# sound.net
KiCad netlist of a schematic drawn in EAGLE
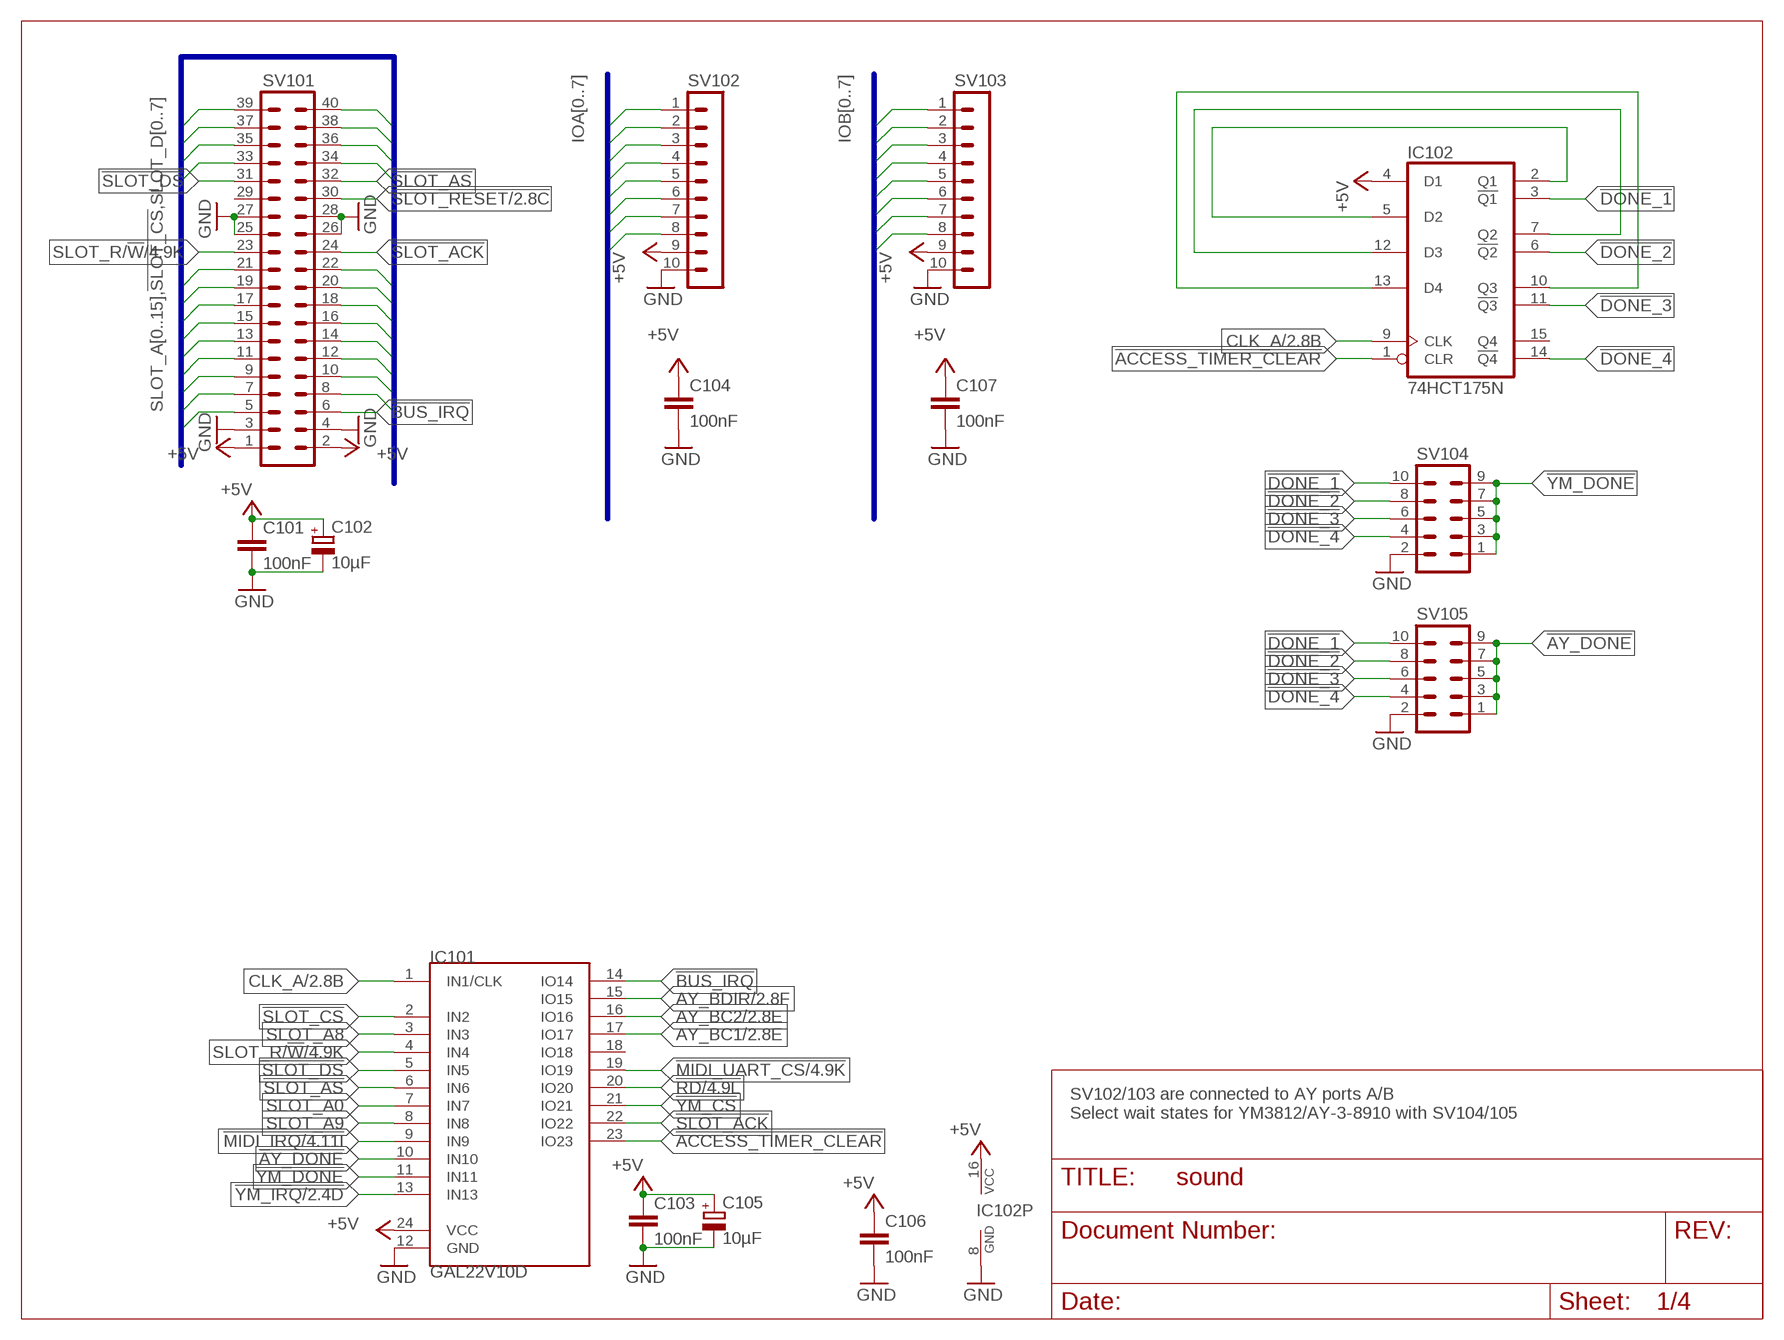
[diagram p0: schematic, sheet 1]
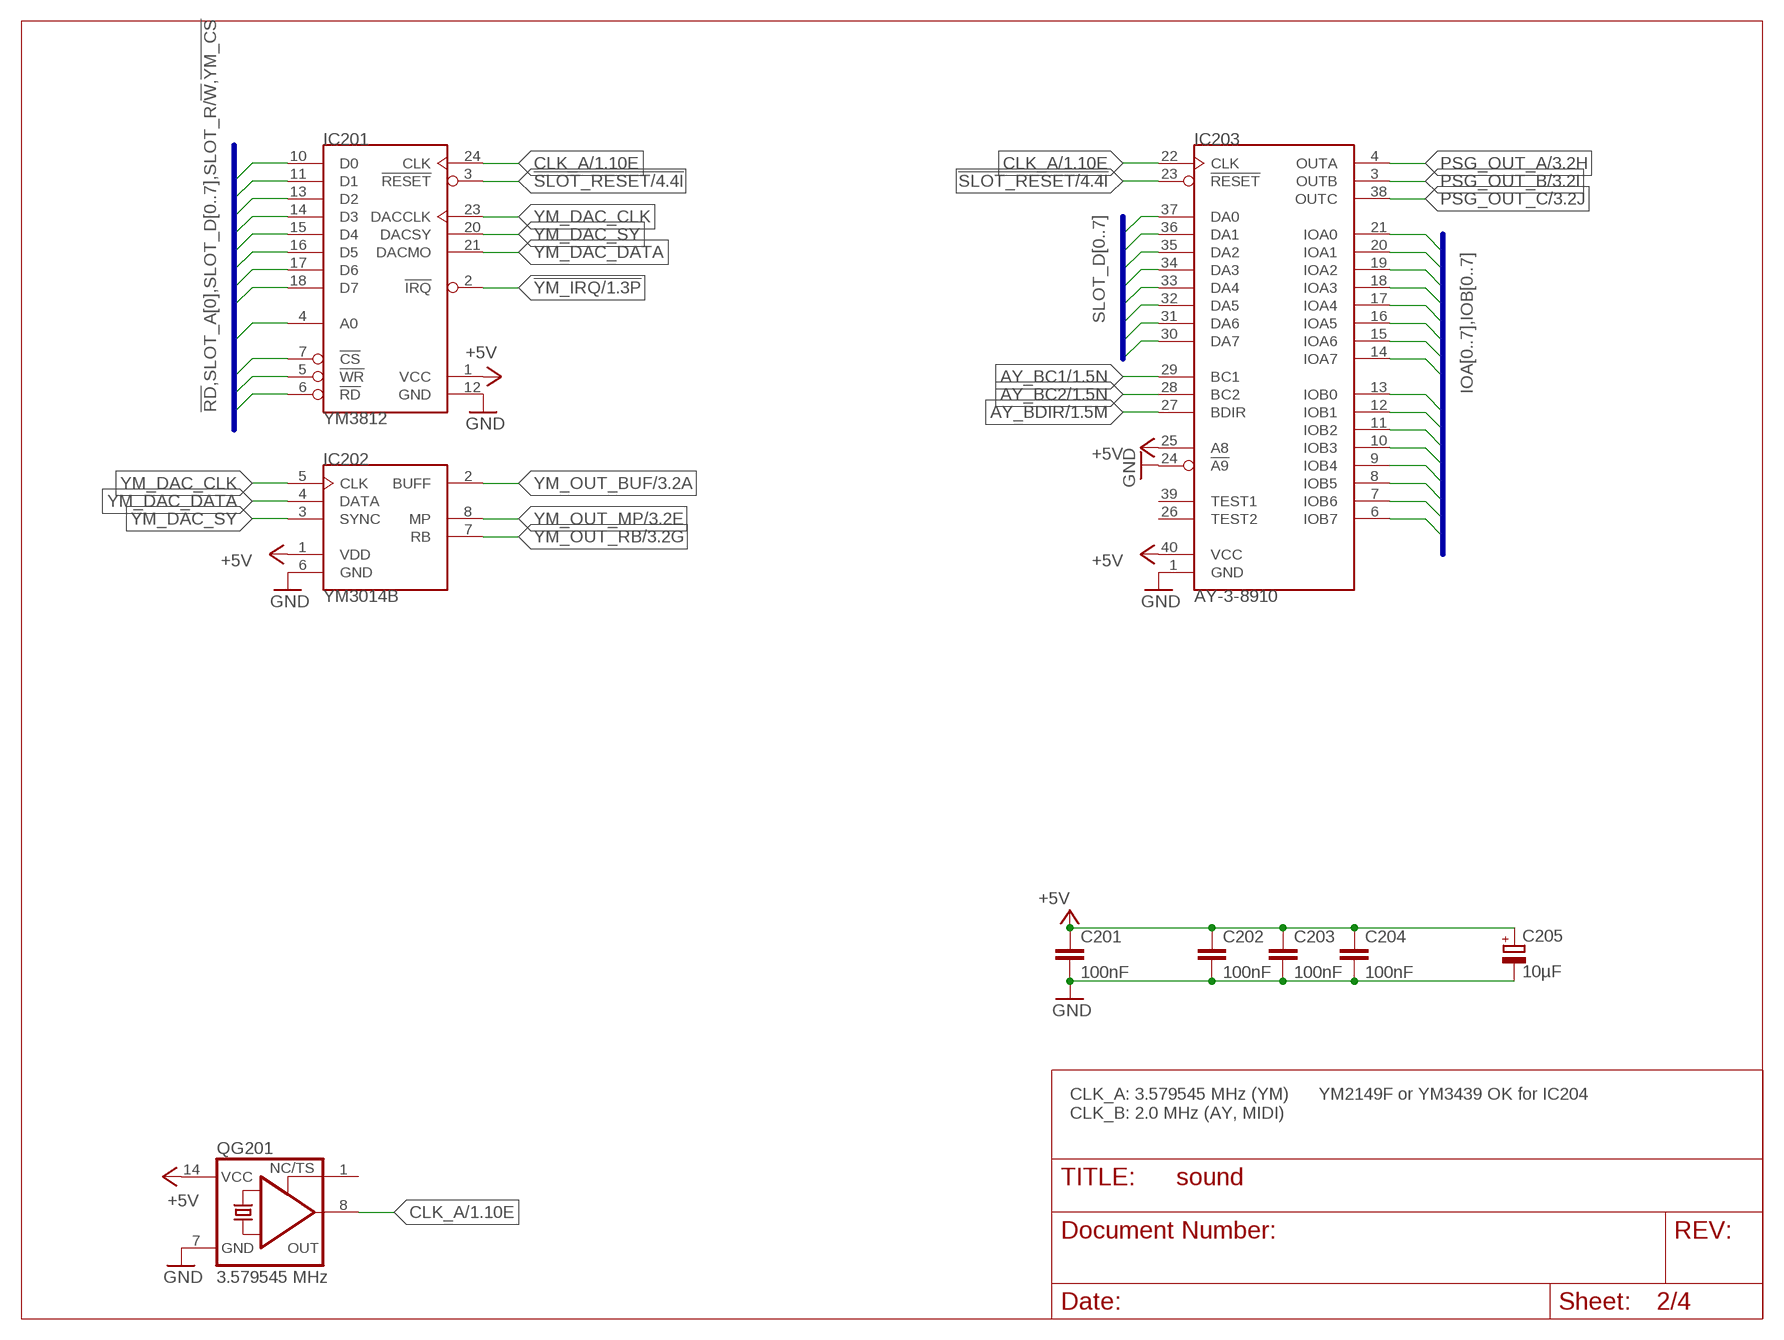
[diagram p1: schematic, sheet 2]
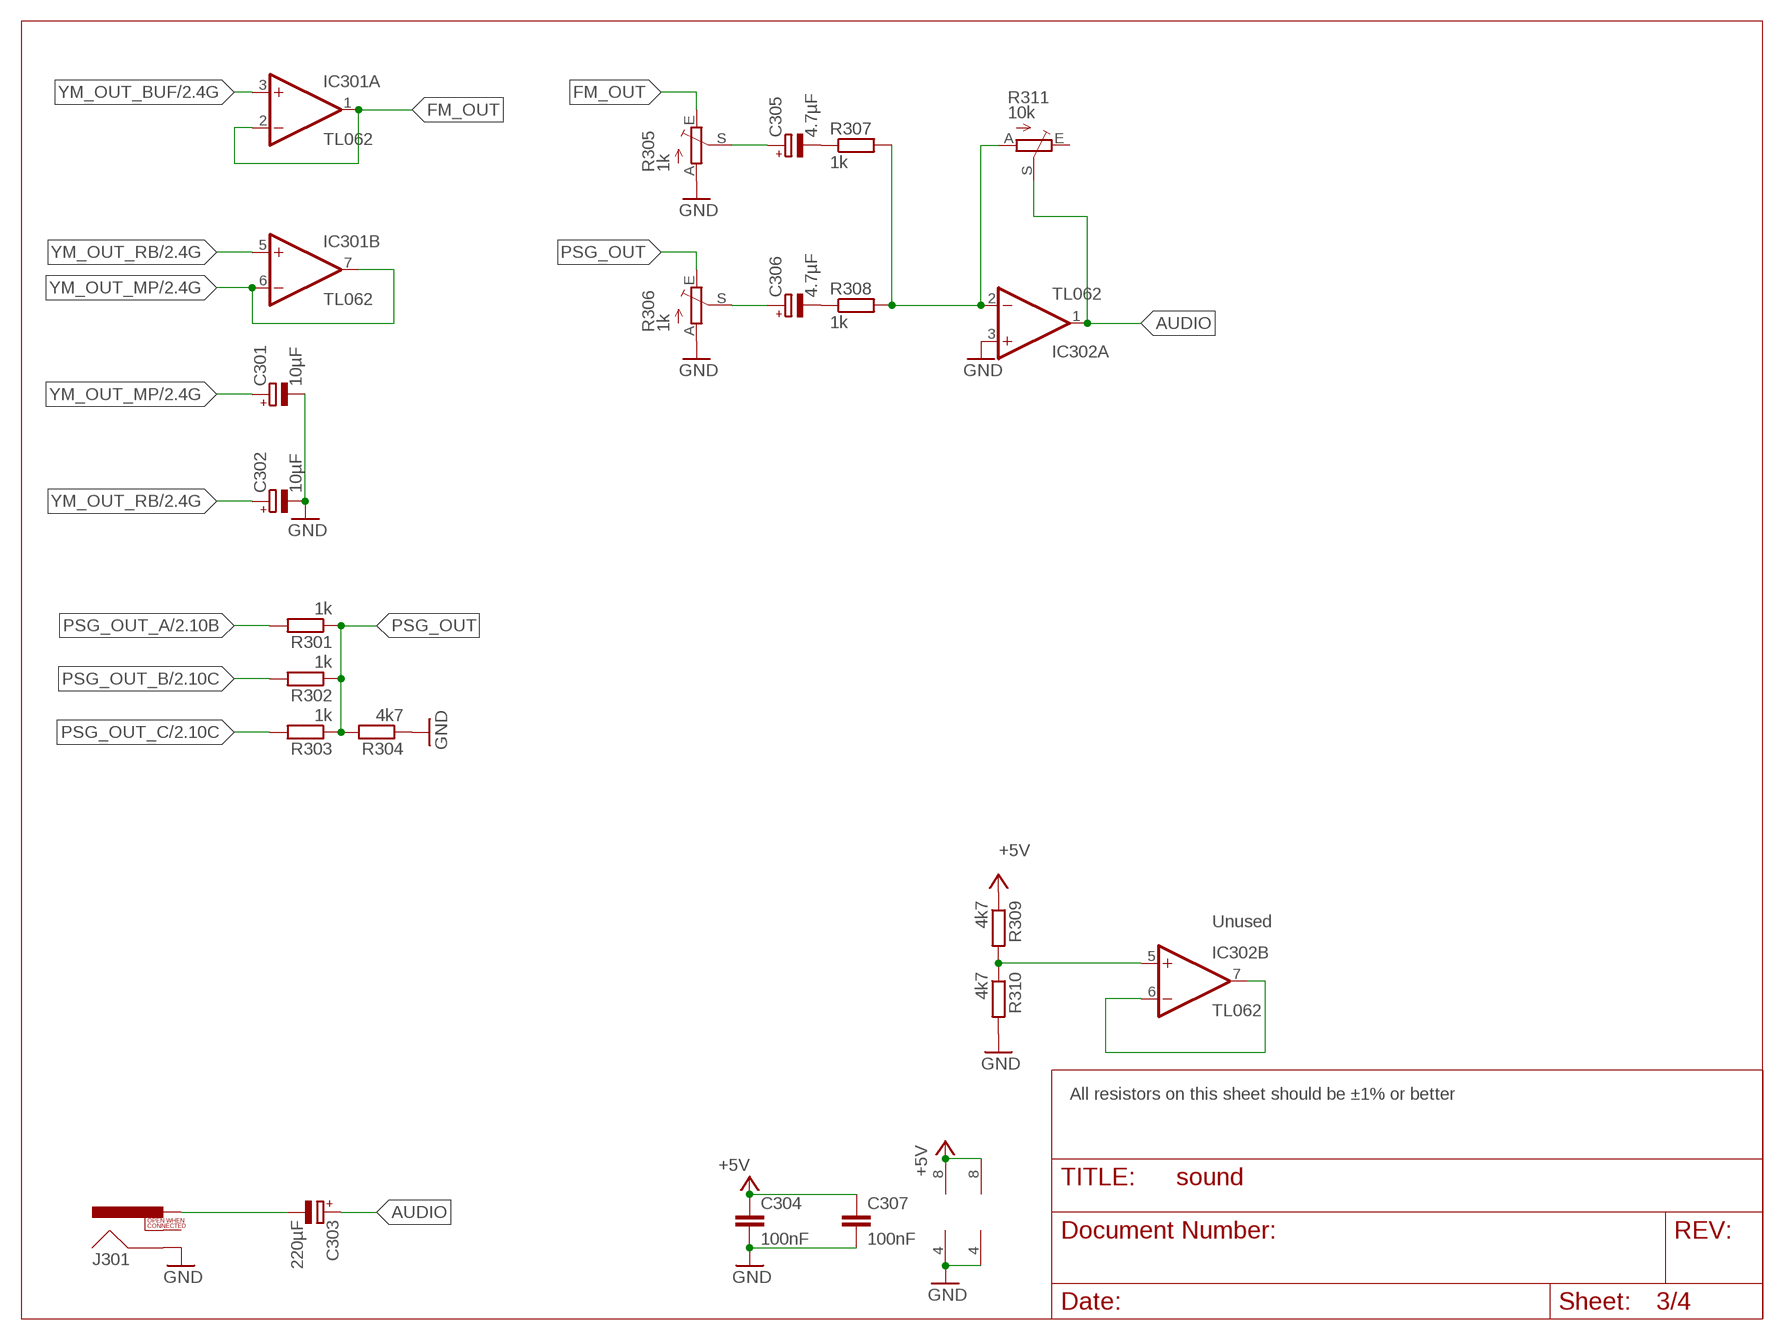
[diagram p2: schematic, sheet 3]
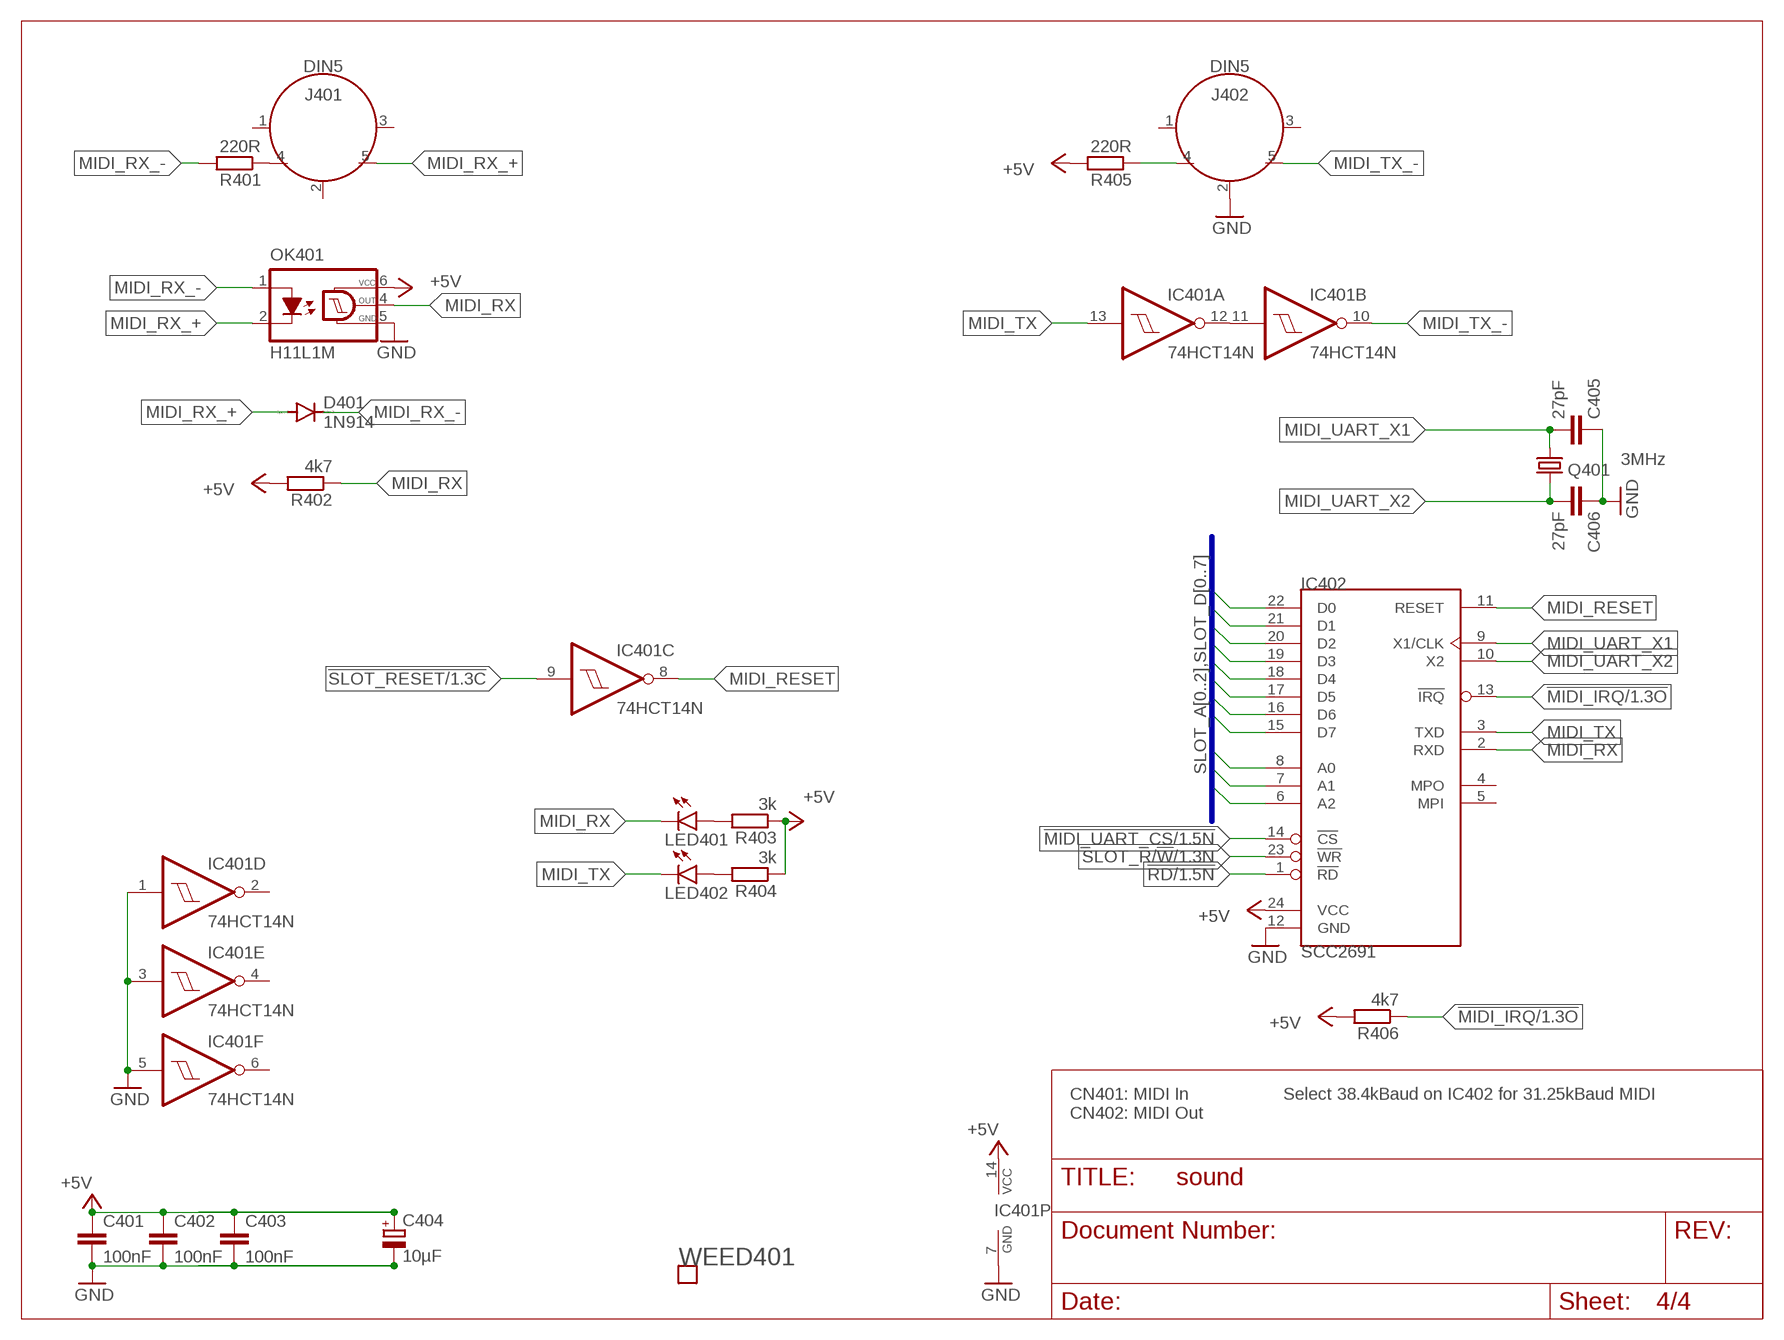
[diagram p3: schematic, sheet 4]

(export (version "E")
  (design (tool "Eeschema 10.0.6"))
  (components
    (comp (ref "C201")
      (value "100nF")
      (footprint "eagle-import:C0805")
      (libsource (lib "eagle-import") (part "C-EUC0805"))
    )
    (comp (ref "C202")
      (value "100nF")
      (footprint "eagle-import:C0805")
      (libsource (lib "eagle-import") (part "C-EUC0805"))
    )
    (comp (ref "C203")
      (value "100nF")
      (footprint "eagle-import:C0805")
      (libsource (lib "eagle-import") (part "C-EUC0805"))
    )
    (comp (ref "C204")
      (value "100nF")
      (footprint "eagle-import:C0805")
      (libsource (lib "eagle-import") (part "C-EUC0805"))
    )
    (comp (ref "C205")
      (value "10µF")
      (footprint "eagle-import:SMC_B")
      (libsource (lib "eagle-import") (part "CPOL-EUSMCB"))
    )
    (comp (ref "IC201")
      (value "YM3812")
      (footprint "eagle-import:DIL24")
      (libsource (lib "eagle-import") (part "YM3812DIL24"))
    )
    (comp (ref "IC202")
      (value "YM3014B")
      (footprint "eagle-import:DIL8")
      (libsource (lib "eagle-import") (part "YM3014BDIL8"))
    )
    (comp (ref "IC203")
      (value "AY-3-8910")
      (footprint "eagle-import:DIL40")
      (libsource (lib "eagle-import") (part "AY-3-8910"))
    )
    (comp (ref "QG201")
      (value "3.579545 MHz")
      (footprint "eagle-import:DIL14S")
      (libsource (lib "eagle-import") (part "XO-14"))
    )
    (comp (ref "C101")
      (value "100nF")
      (footprint "eagle-import:C0805")
      (libsource (lib "eagle-import") (part "C-EUC0805"))
    )
    (comp (ref "C102")
      (value "10µF")
      (footprint "eagle-import:SMC_B")
      (libsource (lib "eagle-import") (part "CPOL-EUSMCB"))
    )
    (comp (ref "C103")
      (value "100nF")
      (footprint "eagle-import:C0805")
      (libsource (lib "eagle-import") (part "C-EUC0805"))
    )
    (comp (ref "C104")
      (value "100nF")
      (footprint "eagle-import:C0805")
      (libsource (lib "eagle-import") (part "C-EUC0805"))
    )
    (comp (ref "C105")
      (value "10µF")
      (footprint "eagle-import:SMC_B")
      (libsource (lib "eagle-import") (part "CPOL-EUSMCB"))
    )
    (comp (ref "C106")
      (value "100nF")
      (footprint "eagle-import:C0805")
      (libsource (lib "eagle-import") (part "C-EUC0805"))
    )
    (comp (ref "C107")
      (value "100nF")
      (footprint "eagle-import:C0805")
      (libsource (lib "eagle-import") (part "C-EUC0805"))
    )
    (comp (ref "IC101")
      (value "GAL22V10D")
      (footprint "eagle-import:DIL24S")
      (libsource (lib "eagle-import") (part "GAL22V10DIP24"))
    )
    (comp (ref "IC102")
      (value "74HCT175N")
      (footprint "eagle-import:DIL16")
      (fields (field (name "MOUSER") "595-CD74HCT175E") (field (name "MOUSER_SOCKET") "575-1104731641001000"))
      (libsource (lib "eagle-import") (part "74175NHCT"))
    )
    (comp (ref "SV101")
      (value "MA20-2W")
      (footprint "eagle-import:MA20-2W")
      (libsource (lib "eagle-import") (part "MA20-2W"))
    )
    (comp (ref "SV102")
      (value "MA10-1")
      (footprint "eagle-import:MA10-1")
      (libsource (lib "eagle-import") (part "MA10-1"))
    )
    (comp (ref "SV103")
      (value "MA10-1")
      (footprint "eagle-import:MA10-1")
      (libsource (lib "eagle-import") (part "MA10-1"))
    )
    (comp (ref "SV104")
      (value "MA05-2")
      (footprint "eagle-import:MA05-2")
      (libsource (lib "eagle-import") (part "MA05-2"))
    )
    (comp (ref "SV105")
      (value "MA05-2")
      (footprint "eagle-import:MA05-2")
      (libsource (lib "eagle-import") (part "MA05-2"))
    )
    (comp (ref "C401")
      (value "100nF")
      (footprint "eagle-import:C0805")
      (libsource (lib "eagle-import") (part "C-EUC0805"))
    )
    (comp (ref "C402")
      (value "100nF")
      (footprint "eagle-import:C0805")
      (libsource (lib "eagle-import") (part "C-EUC0805"))
    )
    (comp (ref "C403")
      (value "100nF")
      (footprint "eagle-import:C0805")
      (libsource (lib "eagle-import") (part "C-EUC0805"))
    )
    (comp (ref "C404")
      (value "10µF")
      (footprint "eagle-import:SMC_B")
      (libsource (lib "eagle-import") (part "CPOL-EUSMCB"))
    )
    (comp (ref "C405")
      (value "27pF")
      (footprint "eagle-import:C0805")
      (libsource (lib "eagle-import") (part "C-EUC0805"))
    )
    (comp (ref "C406")
      (value "27pF")
      (footprint "eagle-import:C0805")
      (libsource (lib "eagle-import") (part "C-EUC0805"))
    )
    (comp (ref "D401")
      (value "1N914")
      (footprint "eagle-import:DO35-10")
      (libsource (lib "eagle-import") (part "1N4148DO35-10"))
    )
    (comp (ref "IC401")
      (value "74HCT14N")
      (footprint "eagle-import:DIL14")
      (fields (field (name "MOUSER") "595-SN74HCT14N") (field (name "MOUSER_SOCKET") "575-1104731441001000"))
      (libsource (lib "eagle-import") (part "7414NHCT"))
    )
    (comp (ref "IC402")
      (value "SCC2691")
      (footprint "eagle-import:DIL24S")
      (libsource (lib "eagle-import") (part "SCC2691"))
    )
    (comp (ref "J401")
      (value "DIN5")
      (footprint "eagle-import:DIN5-RA-PTH")
      (libsource (lib "eagle-import") (part "DIN5"))
    )
    (comp (ref "J402")
      (value "DIN5")
      (footprint "eagle-import:DIN5-RA-PTH")
      (libsource (lib "eagle-import") (part "DIN5"))
    )
    (comp (ref "LED401")
      (value "LEDCHIPLED_1206")
      (footprint "eagle-import:CHIPLED_1206")
      (libsource (lib "eagle-import") (part "LEDCHIPLED_1206"))
    )
    (comp (ref "LED402")
      (value "LEDCHIPLED_1206")
      (footprint "eagle-import:CHIPLED_1206")
      (libsource (lib "eagle-import") (part "LEDCHIPLED_1206"))
    )
    (comp (ref "OK401")
      (value "H11L1M")
      (footprint "eagle-import:DIL06")
      (fields (field (name "MF") "FAIRCHILD SEMICONDUCTOR") (field (name "MPN") "H11L1-M"))
      (libsource (lib "eagle-import") (part "H11LM1"))
    )
    (comp (ref "Q401")
      (value "3MHz")
      (footprint "eagle-import:HC49_S")
      (libsource (lib "eagle-import") (part "CRYSTALHC49S"))
    )
    (comp (ref "R401")
      (value "220R")
      (footprint "eagle-import:R2012")
      (libsource (lib "eagle-import") (part "R-EU_R2012"))
    )
    (comp (ref "R402")
      (value "4k7")
      (footprint "eagle-import:R2012")
      (libsource (lib "eagle-import") (part "R-EU_R2012"))
    )
    (comp (ref "R403")
      (value "3k")
      (footprint "eagle-import:R2012")
      (libsource (lib "eagle-import") (part "R-EU_R2012"))
    )
    (comp (ref "R404")
      (value "3k")
      (footprint "eagle-import:R2012")
      (libsource (lib "eagle-import") (part "R-EU_R2012"))
    )
    (comp (ref "R405")
      (value "220R")
      (footprint "eagle-import:R2012")
      (libsource (lib "eagle-import") (part "R-EU_R2012"))
    )
    (comp (ref "R406")
      (value "4k7")
      (footprint "eagle-import:R2012")
      (libsource (lib "eagle-import") (part "R-EU_R2012"))
    )
    (comp (ref "WEED401")
      (value "WEED")
      (footprint "eagle-import:DOINK")
      (libsource (lib "eagle-import") (part "WEED"))
    )
    (comp (ref "C301")
      (value "10µF")
      (footprint "eagle-import:E2-5")
      (libsource (lib "eagle-import") (part "CPOL-EUE2-5"))
    )
    (comp (ref "C302")
      (value "10µF")
      (footprint "eagle-import:E2-5")
      (libsource (lib "eagle-import") (part "CPOL-EUE2-5"))
    )
    (comp (ref "C303")
      (value "220µF")
      (footprint "eagle-import:E2,5-6")
      (libsource (lib "eagle-import") (part "CPOL-EUE2.5-6"))
    )
    (comp (ref "C304")
      (value "100nF")
      (footprint "eagle-import:C0805")
      (libsource (lib "eagle-import") (part "C-EUC0805"))
    )
    (comp (ref "C305")
      (value "4.7µF")
      (footprint "eagle-import:E2-5")
      (libsource (lib "eagle-import") (part "CPOL-EUE2-5"))
    )
    (comp (ref "C306")
      (value "4.7µF")
      (footprint "eagle-import:E2-5")
      (libsource (lib "eagle-import") (part "CPOL-EUE2-5"))
    )
    (comp (ref "C307")
      (value "100nF")
      (footprint "eagle-import:C0805")
      (libsource (lib "eagle-import") (part "C-EUC0805"))
    )
    (comp (ref "IC301")
      (value "TL062")
      (footprint "eagle-import:DIL08")
      (fields
        (field (name "MOUSER") "595-TL062CP")
        (field (name "MOUSER_SOCKET") "575-1104730841001000")
        (field (name "SPICEPREFIX") "J")
      )
      (libsource (lib "eagle-import") (part "TL062P"))
    )
    (comp (ref "IC302")
      (value "TL062")
      (footprint "eagle-import:DIL08")
      (fields
        (field (name "MOUSER") "595-TL062CP")
        (field (name "MOUSER_SOCKET") "575-1104730841001000")
        (field (name "SPICEPREFIX") "J")
      )
      (libsource (lib "eagle-import") (part "TL062P"))
    )
    (comp (ref "J301")
      (value "RCALOCK")
      (footprint "eagle-import:RCA_LOCK")
      (libsource (lib "eagle-import") (part "RCALOCK"))
    )
    (comp (ref "R301")
      (value "1k")
      (footprint "eagle-import:R2012")
      (libsource (lib "eagle-import") (part "R-EU_R2012"))
    )
    (comp (ref "R302")
      (value "1k")
      (footprint "eagle-import:R2012")
      (libsource (lib "eagle-import") (part "R-EU_R2012"))
    )
    (comp (ref "R303")
      (value "1k")
      (footprint "eagle-import:R2012")
      (libsource (lib "eagle-import") (part "R-EU_R2012"))
    )
    (comp (ref "R304")
      (value "4k7")
      (footprint "eagle-import:R2012")
      (libsource (lib "eagle-import") (part "R-EU_R2012"))
    )
    (comp (ref "R305")
      (value "1k")
      (footprint "eagle-import:PT-10S")
      (fields (field (name "SPICEPREFIX") "J"))
      (libsource (lib "eagle-import") (part "TRIM_EU-PT10S"))
    )
    (comp (ref "R306")
      (value "1k")
      (footprint "eagle-import:PT-10S")
      (fields (field (name "SPICEPREFIX") "J"))
      (libsource (lib "eagle-import") (part "TRIM_EU-PT10S"))
    )
    (comp (ref "R307")
      (value "1k")
      (footprint "eagle-import:R2012")
      (libsource (lib "eagle-import") (part "R-EU_R2012"))
    )
    (comp (ref "R308")
      (value "1k")
      (footprint "eagle-import:R2012")
      (libsource (lib "eagle-import") (part "R-EU_R2012"))
    )
    (comp (ref "R309")
      (value "4k7")
      (footprint "eagle-import:R2012")
      (libsource (lib "eagle-import") (part "R-EU_R2012"))
    )
    (comp (ref "R310")
      (value "4k7")
      (footprint "eagle-import:R2012")
      (libsource (lib "eagle-import") (part "R-EU_R2012"))
    )
    (comp (ref "R311")
      (value "10k")
      (footprint "eagle-import:PT-10S")
      (fields (field (name "SPICEPREFIX") "J"))
      (libsource (lib "eagle-import") (part "TRIM_EU-PT10S"))
    )
  )
  (nets
    (net (code "2") (name "+5V") (class "Default")
      (node (ref "C101") (pin "1") (pinfunction "1_1") (pintype "passive"))
      (node (ref "C102") (pin "+") (pinfunction "+_+") (pintype "passive"))
      (node (ref "C103") (pin "1") (pinfunction "1_1") (pintype "passive"))
      (node (ref "C104") (pin "1") (pinfunction "1_1") (pintype "passive"))
      (node (ref "C105") (pin "+") (pinfunction "+_+") (pintype "passive"))
      (node (ref "C106") (pin "1") (pinfunction "1_1") (pintype "passive"))
      (node (ref "C107") (pin "1") (pinfunction "1_1") (pintype "passive"))
      (node (ref "C201") (pin "1") (pinfunction "1_1") (pintype "passive"))
      (node (ref "C202") (pin "1") (pinfunction "1_1") (pintype "passive"))
      (node (ref "C203") (pin "1") (pinfunction "1_1") (pintype "passive"))
      (node (ref "C204") (pin "1") (pinfunction "1_1") (pintype "passive"))
      (node (ref "C205") (pin "+") (pinfunction "+_+") (pintype "passive"))
      (node (ref "C304") (pin "1") (pinfunction "1_1") (pintype "passive"))
      (node (ref "C307") (pin "1") (pinfunction "1_1") (pintype "passive"))
      (node (ref "C401") (pin "1") (pinfunction "1_1") (pintype "passive"))
      (node (ref "C402") (pin "1") (pinfunction "1_1") (pintype "passive"))
      (node (ref "C403") (pin "1") (pinfunction "1_1") (pintype "passive"))
      (node (ref "C404") (pin "+") (pinfunction "+_+") (pintype "passive"))
      (node (ref "IC101") (pin "24") (pinfunction "VCC_24") (pintype "power_in"))
      (node (ref "IC102") (pin "16") (pinfunction "VCC_16") (pintype "power_in"))
      (node (ref "IC102") (pin "4") (pinfunction "D1_4") (pintype "input"))
      (node (ref "IC201") (pin "1") (pinfunction "VCC_1") (pintype "power_in"))
      (node (ref "IC202") (pin "1") (pinfunction "VDD_1") (pintype "power_in"))
      (node (ref "IC203") (pin "25") (pinfunction "A8_25") (pintype "input"))
      (node (ref "IC203") (pin "40") (pinfunction "VCC_40") (pintype "power_in"))
      (node (ref "IC301") (pin "8") (pinfunction "V+_8") (pintype "power_in"))
      (node (ref "IC302") (pin "8") (pinfunction "V+_8") (pintype "power_in"))
      (node (ref "IC401") (pin "14") (pinfunction "VCC_14") (pintype "power_in"))
      (node (ref "IC402") (pin "24") (pinfunction "VCC_24") (pintype "power_in"))
      (node (ref "OK401") (pin "6") (pinfunction "VCC_6") (pintype "power_in"))
      (node (ref "QG201") (pin "14") (pinfunction "VCC_14") (pintype "power_in"))
      (node (ref "R309") (pin "1") (pinfunction "1_1") (pintype "passive"))
      (node (ref "R402") (pin "2") (pinfunction "2_2") (pintype "passive"))
      (node (ref "R403") (pin "1") (pinfunction "1_1") (pintype "passive"))
      (node (ref "R404") (pin "1") (pinfunction "1_1") (pintype "passive"))
      (node (ref "R405") (pin "2") (pinfunction "2_2") (pintype "passive"))
      (node (ref "R406") (pin "2") (pinfunction "2_2") (pintype "passive"))
      (node (ref "SV101") (pin "1") (pinfunction "1_1") (pintype "passive"))
      (node (ref "SV101") (pin "2") (pinfunction "2_2") (pintype "passive"))
      (node (ref "SV102") (pin "9") (pinfunction "9_9") (pintype "passive"))
      (node (ref "SV103") (pin "9") (pinfunction "9_9") (pintype "passive"))
    )
    (net (code "10") (name "AUDIO") (class "Default")
      (node (ref "C303") (pin "+") (pinfunction "+_+") (pintype "passive"))
      (node (ref "IC302") (pin "1") (pinfunction "OUT_1") (pintype "output"))
      (node (ref "R311") (pin "S") (pinfunction "S_S") (pintype "passive"))
    )
    (net (code "11") (name "AY_BC1") (class "Default")
      (node (ref "IC101") (pin "17") (pinfunction "IO17_17") (pintype "bidirectional"))
      (node (ref "IC203") (pin "29") (pinfunction "BC1_29") (pintype "input"))
    )
    (net (code "12") (name "AY_BC2") (class "Default")
      (node (ref "IC101") (pin "16") (pinfunction "IO16_16") (pintype "bidirectional"))
      (node (ref "IC203") (pin "28") (pinfunction "BC2_28") (pintype "input"))
    )
    (net (code "13") (name "AY_BDIR") (class "Default")
      (node (ref "IC101") (pin "15") (pinfunction "IO15_15") (pintype "bidirectional"))
      (node (ref "IC203") (pin "27") (pinfunction "BDIR_27") (pintype "input"))
    )
    (net (code "14") (name "CLK_A") (class "Default")
      (node (ref "IC101") (pin "1") (pinfunction "IN1/CLK_1") (pintype "input"))
      (node (ref "IC102") (pin "9") (pinfunction "CLK_9") (pintype "input"))
      (node (ref "IC201") (pin "24") (pinfunction "CLK_24") (pintype "input"))
      (node (ref "IC203") (pin "22") (pinfunction "CLK_22") (pintype "input"))
      (node (ref "QG201") (pin "8") (pinfunction "OUT_8") (pintype "output"))
    )
    (net (code "15") (name "FM_OUT") (class "Default")
      (node (ref "IC301") (pin "1") (pinfunction "OUT_1") (pintype "output"))
      (node (ref "IC301") (pin "2") (pinfunction "-IN_2") (pintype "input"))
      (node (ref "R305") (pin "E") (pinfunction "E_E") (pintype "passive"))
    )
    (net (code "16") (name "GND") (class "Default")
      (node (ref "C101") (pin "2") (pinfunction "2_2") (pintype "passive"))
      (node (ref "C102") (pin "-") (pinfunction "-_-") (pintype "passive"))
      (node (ref "C103") (pin "2") (pinfunction "2_2") (pintype "passive"))
      (node (ref "C104") (pin "2") (pinfunction "2_2") (pintype "passive"))
      (node (ref "C105") (pin "-") (pinfunction "-_-") (pintype "passive"))
      (node (ref "C106") (pin "2") (pinfunction "2_2") (pintype "passive"))
      (node (ref "C107") (pin "2") (pinfunction "2_2") (pintype "passive"))
      (node (ref "C201") (pin "2") (pinfunction "2_2") (pintype "passive"))
      (node (ref "C202") (pin "2") (pinfunction "2_2") (pintype "passive"))
      (node (ref "C203") (pin "2") (pinfunction "2_2") (pintype "passive"))
      (node (ref "C204") (pin "2") (pinfunction "2_2") (pintype "passive"))
      (node (ref "C205") (pin "-") (pinfunction "-_-") (pintype "passive"))
      (node (ref "C301") (pin "-") (pinfunction "-_-") (pintype "passive"))
      (node (ref "C302") (pin "-") (pinfunction "-_-") (pintype "passive"))
      (node (ref "C304") (pin "2") (pinfunction "2_2") (pintype "passive"))
      (node (ref "C307") (pin "2") (pinfunction "2_2") (pintype "passive"))
      (node (ref "C401") (pin "2") (pinfunction "2_2") (pintype "passive"))
      (node (ref "C402") (pin "2") (pinfunction "2_2") (pintype "passive"))
      (node (ref "C403") (pin "2") (pinfunction "2_2") (pintype "passive"))
      (node (ref "C404") (pin "-") (pinfunction "-_-") (pintype "passive"))
      (node (ref "C405") (pin "1") (pinfunction "1_1") (pintype "passive"))
      (node (ref "C406") (pin "1") (pinfunction "1_1") (pintype "passive"))
      (node (ref "IC101") (pin "12") (pinfunction "GND_12") (pintype "power_in"))
      (node (ref "IC102") (pin "8") (pinfunction "GND_8") (pintype "power_in"))
      (node (ref "IC201") (pin "12") (pinfunction "GND_12") (pintype "power_in"))
      (node (ref "IC202") (pin "6") (pinfunction "GND_6") (pintype "power_in"))
      (node (ref "IC203") (pin "1") (pinfunction "GND_1") (pintype "power_in"))
      (node (ref "IC203") (pin "24") (pinfunction "~{A9}_24") (pintype "input"))
      (node (ref "IC301") (pin "4") (pinfunction "V-_4") (pintype "power_in"))
      (node (ref "IC302") (pin "3") (pinfunction "+IN_3") (pintype "input"))
      (node (ref "IC302") (pin "4") (pinfunction "V-_4") (pintype "power_in"))
      (node (ref "IC401") (pin "1") (pinfunction "I_1") (pintype "input"))
      (node (ref "IC401") (pin "3") (pinfunction "I_3") (pintype "input"))
      (node (ref "IC401") (pin "5") (pinfunction "I_5") (pintype "input"))
      (node (ref "IC401") (pin "7") (pinfunction "GND_7") (pintype "power_in"))
      (node (ref "IC402") (pin "12") (pinfunction "GND_12") (pintype "power_in"))
      (node (ref "J301") (pin "SHELL") (pinfunction "SHELL_SHELL") (pintype "bidirectional"))
      (node (ref "J402") (pin "2") (pinfunction "2_2") (pintype "bidirectional"))
      (node (ref "OK401") (pin "5") (pinfunction "GND_5") (pintype "power_in"))
      (node (ref "QG201") (pin "7") (pinfunction "GND_7") (pintype "power_in"))
      (node (ref "R304") (pin "1") (pinfunction "1_1") (pintype "passive"))
      (node (ref "R305") (pin "A") (pinfunction "A_A") (pintype "passive"))
      (node (ref "R306") (pin "A") (pinfunction "A_A") (pintype "passive"))
      (node (ref "R310") (pin "2") (pinfunction "2_2") (pintype "passive"))
      (node (ref "SV101") (pin "25") (pinfunction "25_25") (pintype "passive"))
      (node (ref "SV101") (pin "26") (pinfunction "26_26") (pintype "passive"))
      (node (ref "SV101") (pin "27") (pinfunction "27_27") (pintype "passive"))
      (node (ref "SV101") (pin "28") (pinfunction "28_28") (pintype "passive"))
      (node (ref "SV101") (pin "3") (pinfunction "3_3") (pintype "passive"))
      (node (ref "SV101") (pin "4") (pinfunction "4_4") (pintype "passive"))
      (node (ref "SV102") (pin "10") (pinfunction "10_10") (pintype "passive"))
      (node (ref "SV103") (pin "10") (pinfunction "10_10") (pintype "passive"))
      (node (ref "SV104") (pin "2") (pinfunction "2_2") (pintype "passive"))
      (node (ref "SV105") (pin "2") (pinfunction "2_2") (pintype "passive"))
    )
    (net (code "17") (name "IOA0") (class "Default")
      (node (ref "IC203") (pin "21") (pinfunction "IOA0_21") (pintype "bidirectional"))
      (node (ref "SV102") (pin "1") (pinfunction "1_1") (pintype "passive"))
    )
    (net (code "18") (name "IOA1") (class "Default")
      (node (ref "IC203") (pin "20") (pinfunction "IOA1_20") (pintype "bidirectional"))
      (node (ref "SV102") (pin "2") (pinfunction "2_2") (pintype "passive"))
    )
    (net (code "19") (name "IOA2") (class "Default")
      (node (ref "IC203") (pin "19") (pinfunction "IOA2_19") (pintype "bidirectional"))
      (node (ref "SV102") (pin "3") (pinfunction "3_3") (pintype "passive"))
    )
    (net (code "20") (name "IOA3") (class "Default")
      (node (ref "IC203") (pin "18") (pinfunction "IOA3_18") (pintype "bidirectional"))
      (node (ref "SV102") (pin "4") (pinfunction "4_4") (pintype "passive"))
    )
    (net (code "21") (name "IOA4") (class "Default")
      (node (ref "IC203") (pin "17") (pinfunction "IOA4_17") (pintype "bidirectional"))
      (node (ref "SV102") (pin "5") (pinfunction "5_5") (pintype "passive"))
    )
    (net (code "22") (name "IOA5") (class "Default")
      (node (ref "IC203") (pin "16") (pinfunction "IOA5_16") (pintype "bidirectional"))
      (node (ref "SV102") (pin "6") (pinfunction "6_6") (pintype "passive"))
    )
    (net (code "23") (name "IOA6") (class "Default")
      (node (ref "IC203") (pin "15") (pinfunction "IOA6_15") (pintype "bidirectional"))
      (node (ref "SV102") (pin "7") (pinfunction "7_7") (pintype "passive"))
    )
    (net (code "24") (name "IOA7") (class "Default")
      (node (ref "IC203") (pin "14") (pinfunction "IOA7_14") (pintype "bidirectional"))
      (node (ref "SV102") (pin "8") (pinfunction "8_8") (pintype "passive"))
    )
    (net (code "25") (name "IOB0") (class "Default")
      (node (ref "IC203") (pin "13") (pinfunction "IOB0_13") (pintype "bidirectional"))
      (node (ref "SV103") (pin "1") (pinfunction "1_1") (pintype "passive"))
    )
    (net (code "26") (name "IOB1") (class "Default")
      (node (ref "IC203") (pin "12") (pinfunction "IOB1_12") (pintype "bidirectional"))
      (node (ref "SV103") (pin "2") (pinfunction "2_2") (pintype "passive"))
    )
    (net (code "27") (name "IOB2") (class "Default")
      (node (ref "IC203") (pin "11") (pinfunction "IOB2_11") (pintype "bidirectional"))
      (node (ref "SV103") (pin "3") (pinfunction "3_3") (pintype "passive"))
    )
    (net (code "28") (name "IOB3") (class "Default")
      (node (ref "IC203") (pin "10") (pinfunction "IOB3_10") (pintype "bidirectional"))
      (node (ref "SV103") (pin "4") (pinfunction "4_4") (pintype "passive"))
    )
    (net (code "29") (name "IOB4") (class "Default")
      (node (ref "IC203") (pin "9") (pinfunction "IOB4_9") (pintype "bidirectional"))
      (node (ref "SV103") (pin "5") (pinfunction "5_5") (pintype "passive"))
    )
    (net (code "30") (name "IOB5") (class "Default")
      (node (ref "IC203") (pin "8") (pinfunction "IOB5_8") (pintype "bidirectional"))
      (node (ref "SV103") (pin "6") (pinfunction "6_6") (pintype "passive"))
    )
    (net (code "31") (name "IOB6") (class "Default")
      (node (ref "IC203") (pin "7") (pinfunction "IOB6_7") (pintype "bidirectional"))
      (node (ref "SV103") (pin "7") (pinfunction "7_7") (pintype "passive"))
    )
    (net (code "32") (name "IOB7") (class "Default")
      (node (ref "IC203") (pin "6") (pinfunction "IOB7_6") (pintype "bidirectional"))
      (node (ref "SV103") (pin "8") (pinfunction "8_8") (pintype "passive"))
    )
    (net (code "33") (name "MIDI_RESET") (class "Default")
      (node (ref "IC401") (pin "8") (pinfunction "O_8") (pintype "output"))
      (node (ref "IC402") (pin "11") (pinfunction "RESET_11") (pintype "input"))
    )
    (net (code "34") (name "MIDI_RX") (class "Default")
      (node (ref "IC402") (pin "2") (pinfunction "RXD_2") (pintype "input"))
      (node (ref "LED401") (pin "C") (pinfunction "C_C") (pintype "passive"))
      (node (ref "OK401") (pin "4") (pinfunction "OUT_4") (pintype "output"))
      (node (ref "R402") (pin "1") (pinfunction "1_1") (pintype "passive"))
    )
    (net (code "35") (name "MIDI_RX_+") (class "Default")
      (node (ref "D401") (pin "A") (pinfunction "A_A") (pintype "passive"))
      (node (ref "J401") (pin "5") (pinfunction "5_5") (pintype "bidirectional"))
      (node (ref "OK401") (pin "2") (pinfunction "C_2") (pintype "passive"))
    )
    (net (code "36") (name "MIDI_RX_-") (class "Default")
      (node (ref "D401") (pin "C") (pinfunction "C_C") (pintype "passive"))
      (node (ref "OK401") (pin "1") (pinfunction "A_1") (pintype "passive"))
      (node (ref "R401") (pin "2") (pinfunction "2_2") (pintype "passive"))
    )
    (net (code "37") (name "MIDI_TX") (class "Default")
      (node (ref "IC401") (pin "13") (pinfunction "I_13") (pintype "input"))
      (node (ref "IC402") (pin "3") (pinfunction "TXD_3") (pintype "output"))
      (node (ref "LED402") (pin "C") (pinfunction "C_C") (pintype "passive"))
    )
    (net (code "38") (name "MIDI_TX_-") (class "Default")
      (node (ref "IC401") (pin "10") (pinfunction "O_10") (pintype "output"))
      (node (ref "J402") (pin "5") (pinfunction "5_5") (pintype "bidirectional"))
    )
    (net (code "39") (name "MIDI_UART_X1") (class "Default")
      (node (ref "C405") (pin "2") (pinfunction "2_2") (pintype "passive"))
      (node (ref "IC402") (pin "9") (pinfunction "X1/CLK_9") (pintype "passive"))
      (node (ref "Q401") (pin "1") (pinfunction "1_1") (pintype "passive"))
    )
    (net (code "40") (name "MIDI_UART_X2") (class "Default")
      (node (ref "C406") (pin "2") (pinfunction "2_2") (pintype "passive"))
      (node (ref "IC402") (pin "10") (pinfunction "X2_10") (pintype "passive"))
      (node (ref "Q401") (pin "2") (pinfunction "2_2") (pintype "passive"))
    )
    (net (code "41") (name "Net-(C303-Pad-)") (class "Default")
      (node (ref "C303") (pin "-") (pinfunction "-_-") (pintype "passive"))
      (node (ref "J301") (pin "PIN") (pinfunction "PIN_PIN") (pintype "bidirectional"))
    )
    (net (code "42") (name "Net-(C305-Pad+)") (class "Default")
      (node (ref "C305") (pin "+") (pinfunction "+_+") (pintype "passive"))
      (node (ref "R305") (pin "S") (pinfunction "S_S") (pintype "passive"))
    )
    (net (code "43") (name "Net-(C305-Pad-)") (class "Default")
      (node (ref "C305") (pin "-") (pinfunction "-_-") (pintype "passive"))
      (node (ref "R307") (pin "1") (pinfunction "1_1") (pintype "passive"))
    )
    (net (code "44") (name "Net-(C306-Pad+)") (class "Default")
      (node (ref "C306") (pin "+") (pinfunction "+_+") (pintype "passive"))
      (node (ref "R306") (pin "S") (pinfunction "S_S") (pintype "passive"))
    )
    (net (code "45") (name "Net-(C306-Pad-)") (class "Default")
      (node (ref "C306") (pin "-") (pinfunction "-_-") (pintype "passive"))
      (node (ref "R308") (pin "1") (pinfunction "1_1") (pintype "passive"))
    )
    (net (code "46") (name "Net-(IC102A-D2)") (class "Default")
      (node (ref "IC102") (pin "2") (pinfunction "Q1_2") (pintype "output"))
      (node (ref "IC102") (pin "5") (pinfunction "D2_5") (pintype "input"))
    )
    (net (code "47") (name "Net-(IC102A-D3)") (class "Default")
      (node (ref "IC102") (pin "12") (pinfunction "D3_12") (pintype "input"))
      (node (ref "IC102") (pin "7") (pinfunction "Q2_7") (pintype "output"))
    )
    (net (code "48") (name "Net-(IC102A-D4)") (class "Default")
      (node (ref "IC102") (pin "10") (pinfunction "Q3_10") (pintype "output"))
      (node (ref "IC102") (pin "13") (pinfunction "D4_13") (pintype "input"))
    )
    (net (code "49") (name "Net-(IC302A--IN)") (class "Default")
      (node (ref "IC302") (pin "2") (pinfunction "-IN_2") (pintype "input"))
      (node (ref "R307") (pin "2") (pinfunction "2_2") (pintype "passive"))
      (node (ref "R308") (pin "2") (pinfunction "2_2") (pintype "passive"))
      (node (ref "R311") (pin "A") (pinfunction "A_A") (pintype "passive"))
    )
    (net (code "50") (name "Net-(IC302B-+IN)") (class "Default")
      (node (ref "IC302") (pin "5") (pinfunction "+IN_5") (pintype "input"))
      (node (ref "R309") (pin "2") (pinfunction "2_2") (pintype "passive"))
      (node (ref "R310") (pin "1") (pinfunction "1_1") (pintype "passive"))
    )
    (net (code "51") (name "Net-(IC302B--IN)") (class "Default")
      (node (ref "IC302") (pin "6") (pinfunction "-IN_6") (pintype "input"))
      (node (ref "IC302") (pin "7") (pinfunction "OUT_7") (pintype "output"))
    )
    (net (code "52") (name "Net-(IC401A-O)") (class "Default")
      (node (ref "IC401") (pin "11") (pinfunction "I_11") (pintype "input"))
      (node (ref "IC401") (pin "12") (pinfunction "O_12") (pintype "output"))
    )
    (net (code "53") (name "Net-(J401-Pad4)") (class "Default")
      (node (ref "J401") (pin "4") (pinfunction "4_4") (pintype "bidirectional"))
      (node (ref "R401") (pin "1") (pinfunction "1_1") (pintype "passive"))
    )
    (net (code "54") (name "Net-(J402-Pad4)") (class "Default")
      (node (ref "J402") (pin "4") (pinfunction "4_4") (pintype "bidirectional"))
      (node (ref "R405") (pin "1") (pinfunction "1_1") (pintype "passive"))
    )
    (net (code "55") (name "Net-(LED401-PadA)") (class "Default")
      (node (ref "LED401") (pin "A") (pinfunction "A_A") (pintype "passive"))
      (node (ref "R403") (pin "2") (pinfunction "2_2") (pintype "passive"))
    )
    (net (code "56") (name "Net-(LED402-PadA)") (class "Default")
      (node (ref "LED402") (pin "A") (pinfunction "A_A") (pintype "passive"))
      (node (ref "R404") (pin "2") (pinfunction "2_2") (pintype "passive"))
    )
    (net (code "57") (name "PSG_OUT") (class "Default")
      (node (ref "R301") (pin "1") (pinfunction "1_1") (pintype "passive"))
      (node (ref "R302") (pin "1") (pinfunction "1_1") (pintype "passive"))
      (node (ref "R303") (pin "1") (pinfunction "1_1") (pintype "passive"))
      (node (ref "R304") (pin "2") (pinfunction "2_2") (pintype "passive"))
      (node (ref "R306") (pin "E") (pinfunction "E_E") (pintype "passive"))
    )
    (net (code "58") (name "PSG_OUT_A") (class "Default")
      (node (ref "IC203") (pin "4") (pinfunction "OUTA_4") (pintype "output"))
      (node (ref "R301") (pin "2") (pinfunction "2_2") (pintype "passive"))
    )
    (net (code "59") (name "PSG_OUT_B") (class "Default")
      (node (ref "IC203") (pin "3") (pinfunction "OUTB_3") (pintype "output"))
      (node (ref "R302") (pin "2") (pinfunction "2_2") (pintype "passive"))
    )
    (net (code "60") (name "PSG_OUT_C") (class "Default")
      (node (ref "IC203") (pin "38") (pinfunction "OUTC_38") (pintype "output"))
      (node (ref "R303") (pin "2") (pinfunction "2_2") (pintype "passive"))
    )
    (net (code "61") (name "SLOT_A0") (class "Default")
      (node (ref "IC101") (pin "7") (pinfunction "IN7_7") (pintype "input"))
      (node (ref "IC201") (pin "4") (pinfunction "A0_4") (pintype "input"))
      (node (ref "IC402") (pin "8") (pinfunction "A0_8") (pintype "input"))
      (node (ref "SV101") (pin "12") (pinfunction "12_12") (pintype "passive"))
    )
    (net (code "62") (name "SLOT_A1") (class "Default")
      (node (ref "IC402") (pin "7") (pinfunction "A1_7") (pintype "input"))
      (node (ref "SV101") (pin "10") (pinfunction "10_10") (pintype "passive"))
    )
    (net (code "63") (name "SLOT_A2") (class "Default")
      (node (ref "IC402") (pin "6") (pinfunction "A2_6") (pintype "input"))
      (node (ref "SV101") (pin "8") (pinfunction "8_8") (pintype "passive"))
    )
    (net (code "64") (name "SLOT_A8") (class "Default")
      (node (ref "IC101") (pin "3") (pinfunction "IN3_3") (pintype "input"))
      (node (ref "SV101") (pin "16") (pinfunction "16_16") (pintype "passive"))
    )
    (net (code "65") (name "SLOT_A9") (class "Default")
      (node (ref "IC101") (pin "8") (pinfunction "IN8_8") (pintype "input"))
      (node (ref "SV101") (pin "15") (pinfunction "15_15") (pintype "passive"))
    )
    (net (code "66") (name "SLOT_D0") (class "Default")
      (node (ref "IC201") (pin "10") (pinfunction "D0_10") (pintype "bidirectional"))
      (node (ref "IC203") (pin "37") (pinfunction "DA0_37") (pintype "bidirectional"))
      (node (ref "IC402") (pin "22") (pinfunction "D0_22") (pintype "bidirectional"))
      (node (ref "SV101") (pin "35") (pinfunction "35_35") (pintype "passive"))
    )
    (net (code "67") (name "SLOT_D1") (class "Default")
      (node (ref "IC201") (pin "11") (pinfunction "D1_11") (pintype "bidirectional"))
      (node (ref "IC203") (pin "36") (pinfunction "DA1_36") (pintype "bidirectional"))
      (node (ref "IC402") (pin "21") (pinfunction "D1_21") (pintype "bidirectional"))
      (node (ref "SV101") (pin "37") (pinfunction "37_37") (pintype "passive"))
    )
    (net (code "68") (name "SLOT_D2") (class "Default")
      (node (ref "IC201") (pin "13") (pinfunction "D2_13") (pintype "bidirectional"))
      (node (ref "IC203") (pin "35") (pinfunction "DA2_35") (pintype "bidirectional"))
      (node (ref "IC402") (pin "20") (pinfunction "D2_20") (pintype "bidirectional"))
      (node (ref "SV101") (pin "39") (pinfunction "39_39") (pintype "passive"))
    )
    (net (code "69") (name "SLOT_D3") (class "Default")
      (node (ref "IC201") (pin "14") (pinfunction "D3_14") (pintype "bidirectional"))
      (node (ref "IC203") (pin "34") (pinfunction "DA3_34") (pintype "bidirectional"))
      (node (ref "IC402") (pin "19") (pinfunction "D3_19") (pintype "bidirectional"))
      (node (ref "SV101") (pin "40") (pinfunction "40_40") (pintype "passive"))
    )
    (net (code "70") (name "SLOT_D4") (class "Default")
      (node (ref "IC201") (pin "15") (pinfunction "D4_15") (pintype "bidirectional"))
      (node (ref "IC203") (pin "33") (pinfunction "DA4_33") (pintype "bidirectional"))
      (node (ref "IC402") (pin "18") (pinfunction "D4_18") (pintype "bidirectional"))
      (node (ref "SV101") (pin "38") (pinfunction "38_38") (pintype "passive"))
    )
    (net (code "71") (name "SLOT_D5") (class "Default")
      (node (ref "IC201") (pin "16") (pinfunction "D5_16") (pintype "bidirectional"))
      (node (ref "IC203") (pin "32") (pinfunction "DA5_32") (pintype "bidirectional"))
      (node (ref "IC402") (pin "17") (pinfunction "D5_17") (pintype "bidirectional"))
      (node (ref "SV101") (pin "36") (pinfunction "36_36") (pintype "passive"))
    )
    (net (code "72") (name "SLOT_D6") (class "Default")
      (node (ref "IC201") (pin "17") (pinfunction "D6_17") (pintype "bidirectional"))
      (node (ref "IC203") (pin "31") (pinfunction "DA6_31") (pintype "bidirectional"))
      (node (ref "IC402") (pin "16") (pinfunction "D6_16") (pintype "bidirectional"))
      (node (ref "SV101") (pin "34") (pinfunction "34_34") (pintype "passive"))
    )
    (net (code "73") (name "SLOT_D7") (class "Default")
      (node (ref "IC201") (pin "18") (pinfunction "D7_18") (pintype "bidirectional"))
      (node (ref "IC203") (pin "30") (pinfunction "DA7_30") (pintype "bidirectional"))
      (node (ref "IC402") (pin "15") (pinfunction "D7_15") (pintype "bidirectional"))
      (node (ref "SV101") (pin "33") (pinfunction "33_33") (pintype "passive"))
    )
    (net (code "74") (name "SLOT_R{slash}~{W}") (class "Default")
      (node (ref "IC101") (pin "4") (pinfunction "IN4_4") (pintype "input"))
      (node (ref "IC201") (pin "5") (pinfunction "~{WR}_5") (pintype "input"))
      (node (ref "IC402") (pin "23") (pinfunction "~{WR}_23") (pintype "input"))
      (node (ref "SV101") (pin "23") (pinfunction "23_23") (pintype "passive"))
    )
    (net (code "75") (name "YM_DAC_CLK") (class "Default")
      (node (ref "IC201") (pin "23") (pinfunction "DACCLK_23") (pintype "output"))
      (node (ref "IC202") (pin "5") (pinfunction "CLK_5") (pintype "input"))
    )
    (net (code "76") (name "YM_DAC_DATA") (class "Default")
      (node (ref "IC201") (pin "21") (pinfunction "DACMO_21") (pintype "output"))
      (node (ref "IC202") (pin "4") (pinfunction "DATA_4") (pintype "input"))
    )
    (net (code "77") (name "YM_DAC_SY") (class "Default")
      (node (ref "IC201") (pin "20") (pinfunction "DACSY_20") (pintype "output"))
      (node (ref "IC202") (pin "3") (pinfunction "SYNC_3") (pintype "input"))
    )
    (net (code "78") (name "YM_OUT_BUF") (class "Default")
      (node (ref "IC202") (pin "2") (pinfunction "BUFF_2") (pintype "output"))
      (node (ref "IC301") (pin "3") (pinfunction "+IN_3") (pintype "input"))
    )
    (net (code "79") (name "YM_OUT_MP") (class "Default")
      (node (ref "C301") (pin "+") (pinfunction "+_+") (pintype "passive"))
      (node (ref "IC202") (pin "8") (pinfunction "MP_8") (pintype "output"))
      (node (ref "IC301") (pin "6") (pinfunction "-IN_6") (pintype "input"))
      (node (ref "IC301") (pin "7") (pinfunction "OUT_7") (pintype "output"))
    )
    (net (code "80") (name "YM_OUT_RB") (class "Default")
      (node (ref "C302") (pin "+") (pinfunction "+_+") (pintype "passive"))
      (node (ref "IC202") (pin "7") (pinfunction "RB_7") (pintype "output"))
      (node (ref "IC301") (pin "5") (pinfunction "+IN_5") (pintype "input"))
    )
    (net (code "81") (name "unconnected-(IC101-IO18-Pad18)") (class "Default")
      (node (ref "IC101") (pin "18") (pinfunction "IO18_18") (pintype "bidirectional"))
    )
    (net (code "82") (name "unconnected-(IC102A-Q4-Pad15)") (class "Default")
      (node (ref "IC102") (pin "15") (pinfunction "Q4_15") (pintype "output"))
    )
    (net (code "83") (name "unconnected-(IC203-TEST1-Pad39)") (class "Default")
      (node (ref "IC203") (pin "39") (pinfunction "TEST1_39") (pintype "passive"))
    )
    (net (code "84") (name "unconnected-(IC203-TEST2-Pad26)") (class "Default")
      (node (ref "IC203") (pin "26") (pinfunction "TEST2_26") (pintype "passive"))
    )
    (net (code "85") (name "unconnected-(IC401D-O-Pad2)") (class "Default")
      (node (ref "IC401") (pin "2") (pinfunction "O_2") (pintype "output"))
    )
    (net (code "86") (name "unconnected-(IC401E-O-Pad4)") (class "Default")
      (node (ref "IC401") (pin "4") (pinfunction "O_4") (pintype "output"))
    )
    (net (code "87") (name "unconnected-(IC401F-O-Pad6)") (class "Default")
      (node (ref "IC401") (pin "6") (pinfunction "O_6") (pintype "output"))
    )
    (net (code "88") (name "unconnected-(IC402-MPI-Pad5)") (class "Default")
      (node (ref "IC402") (pin "5") (pinfunction "MPI_5") (pintype "input"))
    )
    (net (code "89") (name "unconnected-(IC402-MPO-Pad4)") (class "Default")
      (node (ref "IC402") (pin "4") (pinfunction "MPO_4") (pintype "output"))
    )
    (net (code "90") (name "unconnected-(J301-PadSWITCH)") (class "Default")
      (node (ref "J301") (pin "SWITCH") (pinfunction "SWITCH_SWITCH") (pintype "bidirectional"))
    )
    (net (code "91") (name "unconnected-(J401-Pad1)") (class "Default")
      (node (ref "J401") (pin "1") (pinfunction "1_1") (pintype "bidirectional"))
    )
    (net (code "92") (name "unconnected-(J401-Pad2)") (class "Default")
      (node (ref "J401") (pin "2") (pinfunction "2_2") (pintype "bidirectional"))
    )
    (net (code "93") (name "unconnected-(J401-Pad3)") (class "Default")
      (node (ref "J401") (pin "3") (pinfunction "3_3") (pintype "bidirectional"))
    )
    (net (code "94") (name "unconnected-(J402-Pad1)") (class "Default")
      (node (ref "J402") (pin "1") (pinfunction "1_1") (pintype "bidirectional"))
    )
    (net (code "95") (name "unconnected-(J402-Pad3)") (class "Default")
      (node (ref "J402") (pin "3") (pinfunction "3_3") (pintype "bidirectional"))
    )
    (net (code "96") (name "unconnected-(QG201-TS-Pad1)") (class "Default")
      (node (ref "QG201") (pin "1") (pinfunction "TS_1") (pintype "passive"))
    )
    (net (code "97") (name "unconnected-(R311-PadE)") (class "Default")
      (node (ref "R311") (pin "E") (pinfunction "E_E") (pintype "passive"))
    )
    (net (code "98") (name "unconnected-(SV101-Pad7)") (class "Default")
      (node (ref "SV101") (pin "7") (pinfunction "7_7") (pintype "passive"))
    )
    (net (code "99") (name "unconnected-(SV101-Pad9)") (class "Default")
      (node (ref "SV101") (pin "9") (pinfunction "9_9") (pintype "passive"))
    )
    (net (code "100") (name "unconnected-(SV101-Pad11)") (class "Default")
      (node (ref "SV101") (pin "11") (pinfunction "11_11") (pintype "passive"))
    )
    (net (code "101") (name "unconnected-(SV101-Pad13)") (class "Default")
      (node (ref "SV101") (pin "13") (pinfunction "13_13") (pintype "passive"))
    )
    (net (code "102") (name "unconnected-(SV101-Pad14)") (class "Default")
      (node (ref "SV101") (pin "14") (pinfunction "14_14") (pintype "passive"))
    )
    (net (code "103") (name "unconnected-(SV101-Pad17)") (class "Default")
      (node (ref "SV101") (pin "17") (pinfunction "17_17") (pintype "passive"))
    )
    (net (code "104") (name "unconnected-(SV101-Pad18)") (class "Default")
      (node (ref "SV101") (pin "18") (pinfunction "18_18") (pintype "passive"))
    )
    (net (code "105") (name "unconnected-(SV101-Pad19)") (class "Default")
      (node (ref "SV101") (pin "19") (pinfunction "19_19") (pintype "passive"))
    )
    (net (code "106") (name "unconnected-(SV101-Pad20)") (class "Default")
      (node (ref "SV101") (pin "20") (pinfunction "20_20") (pintype "passive"))
    )
    (net (code "107") (name "unconnected-(SV101-Pad21)") (class "Default")
      (node (ref "SV101") (pin "21") (pinfunction "21_21") (pintype "passive"))
    )
    (net (code "108") (name "unconnected-(SV101-Pad22)") (class "Default")
      (node (ref "SV101") (pin "22") (pinfunction "22_22") (pintype "passive"))
    )
    (net (code "109") (name "unconnected-(SV101-Pad29)") (class "Default")
      (node (ref "SV101") (pin "29") (pinfunction "29_29") (pintype "passive"))
    )
    (net (code "110") (name "~{ACCESS_TIMER_CLEAR}") (class "Default")
      (node (ref "IC101") (pin "23") (pinfunction "IO23_23") (pintype "bidirectional"))
      (node (ref "IC102") (pin "1") (pinfunction "CLR_1") (pintype "input"))
    )
    (net (code "111") (name "~{AY_DONE}") (class "Default")
      (node (ref "IC101") (pin "10") (pinfunction "IN10_10") (pintype "input"))
      (node (ref "SV105") (pin "1") (pinfunction "1_1") (pintype "passive"))
      (node (ref "SV105") (pin "3") (pinfunction "3_3") (pintype "passive"))
      (node (ref "SV105") (pin "5") (pinfunction "5_5") (pintype "passive"))
      (node (ref "SV105") (pin "7") (pinfunction "7_7") (pintype "passive"))
      (node (ref "SV105") (pin "9") (pinfunction "9_9") (pintype "passive"))
    )
    (net (code "112") (name "~{BUS_IRQ}") (class "Default")
      (node (ref "IC101") (pin "14") (pinfunction "IO14_14") (pintype "bidirectional"))
      (node (ref "SV101") (pin "6") (pinfunction "6_6") (pintype "passive"))
    )
    (net (code "113") (name "~{DONE_1}") (class "Default")
      (node (ref "IC102") (pin "3") (pinfunction "~{Q1}_3") (pintype "output"))
      (node (ref "SV104") (pin "10") (pinfunction "10_10") (pintype "passive"))
      (node (ref "SV105") (pin "10") (pinfunction "10_10") (pintype "passive"))
    )
    (net (code "114") (name "~{DONE_2}") (class "Default")
      (node (ref "IC102") (pin "6") (pinfunction "~{Q2}_6") (pintype "output"))
      (node (ref "SV104") (pin "8") (pinfunction "8_8") (pintype "passive"))
      (node (ref "SV105") (pin "8") (pinfunction "8_8") (pintype "passive"))
    )
    (net (code "115") (name "~{DONE_3}") (class "Default")
      (node (ref "IC102") (pin "11") (pinfunction "~{Q3}_11") (pintype "output"))
      (node (ref "SV104") (pin "6") (pinfunction "6_6") (pintype "passive"))
      (node (ref "SV105") (pin "6") (pinfunction "6_6") (pintype "passive"))
    )
    (net (code "116") (name "~{DONE_4}") (class "Default")
      (node (ref "IC102") (pin "14") (pinfunction "~{Q4}_14") (pintype "output"))
      (node (ref "SV104") (pin "4") (pinfunction "4_4") (pintype "passive"))
      (node (ref "SV105") (pin "4") (pinfunction "4_4") (pintype "passive"))
    )
    (net (code "117") (name "~{MIDI_IRQ}") (class "Default")
      (node (ref "IC101") (pin "9") (pinfunction "IN9_9") (pintype "input"))
      (node (ref "IC402") (pin "13") (pinfunction "~{IRQ}_13") (pintype "output"))
      (node (ref "R406") (pin "1") (pinfunction "1_1") (pintype "passive"))
    )
    (net (code "118") (name "~{MIDI_UART_CS}") (class "Default")
      (node (ref "IC101") (pin "19") (pinfunction "IO19_19") (pintype "bidirectional"))
      (node (ref "IC402") (pin "14") (pinfunction "~{CS}_14") (pintype "input"))
    )
    (net (code "119") (name "~{RD}") (class "Default")
      (node (ref "IC101") (pin "20") (pinfunction "IO20_20") (pintype "bidirectional"))
      (node (ref "IC201") (pin "6") (pinfunction "~{RD}_6") (pintype "input"))
      (node (ref "IC402") (pin "1") (pinfunction "~{RD}_1") (pintype "input"))
    )
    (net (code "120") (name "~{SLOT_ACK}") (class "Default")
      (node (ref "IC101") (pin "22") (pinfunction "IO22_22") (pintype "bidirectional"))
      (node (ref "SV101") (pin "24") (pinfunction "24_24") (pintype "passive"))
    )
    (net (code "121") (name "~{SLOT_AS}") (class "Default")
      (node (ref "IC101") (pin "6") (pinfunction "IN6_6") (pintype "input"))
      (node (ref "SV101") (pin "32") (pinfunction "32_32") (pintype "passive"))
    )
    (net (code "122") (name "~{SLOT_CS}") (class "Default")
      (node (ref "IC101") (pin "2") (pinfunction "IN2_2") (pintype "input"))
      (node (ref "SV101") (pin "5") (pinfunction "5_5") (pintype "passive"))
    )
    (net (code "123") (name "~{SLOT_DS}") (class "Default")
      (node (ref "IC101") (pin "5") (pinfunction "IN5_5") (pintype "input"))
      (node (ref "SV101") (pin "31") (pinfunction "31_31") (pintype "passive"))
    )
    (net (code "124") (name "~{SLOT_RESET}") (class "Default")
      (node (ref "IC201") (pin "3") (pinfunction "~{RESET}_3") (pintype "input"))
      (node (ref "IC203") (pin "23") (pinfunction "~{RESET}_23") (pintype "input"))
      (node (ref "IC401") (pin "9") (pinfunction "I_9") (pintype "input"))
      (node (ref "SV101") (pin "30") (pinfunction "30_30") (pintype "passive"))
    )
    (net (code "125") (name "~{YM_CS}") (class "Default")
      (node (ref "IC101") (pin "21") (pinfunction "IO21_21") (pintype "bidirectional"))
      (node (ref "IC201") (pin "7") (pinfunction "~{CS}_7") (pintype "input"))
    )
    (net (code "126") (name "~{YM_DONE}") (class "Default")
      (node (ref "IC101") (pin "11") (pinfunction "IN11_11") (pintype "input"))
      (node (ref "SV104") (pin "1") (pinfunction "1_1") (pintype "passive"))
      (node (ref "SV104") (pin "3") (pinfunction "3_3") (pintype "passive"))
      (node (ref "SV104") (pin "5") (pinfunction "5_5") (pintype "passive"))
      (node (ref "SV104") (pin "7") (pinfunction "7_7") (pintype "passive"))
      (node (ref "SV104") (pin "9") (pinfunction "9_9") (pintype "passive"))
    )
    (net (code "127") (name "~{YM_IRQ}") (class "Default")
      (node (ref "IC101") (pin "13") (pinfunction "IN13_13") (pintype "input"))
      (node (ref "IC201") (pin "2") (pinfunction "~{IRQ}_2") (pintype "output"))
    )
  )
)
